# 4_port_powered_backplane.net
KiCad netlist of a schematic drawn in EAGLE
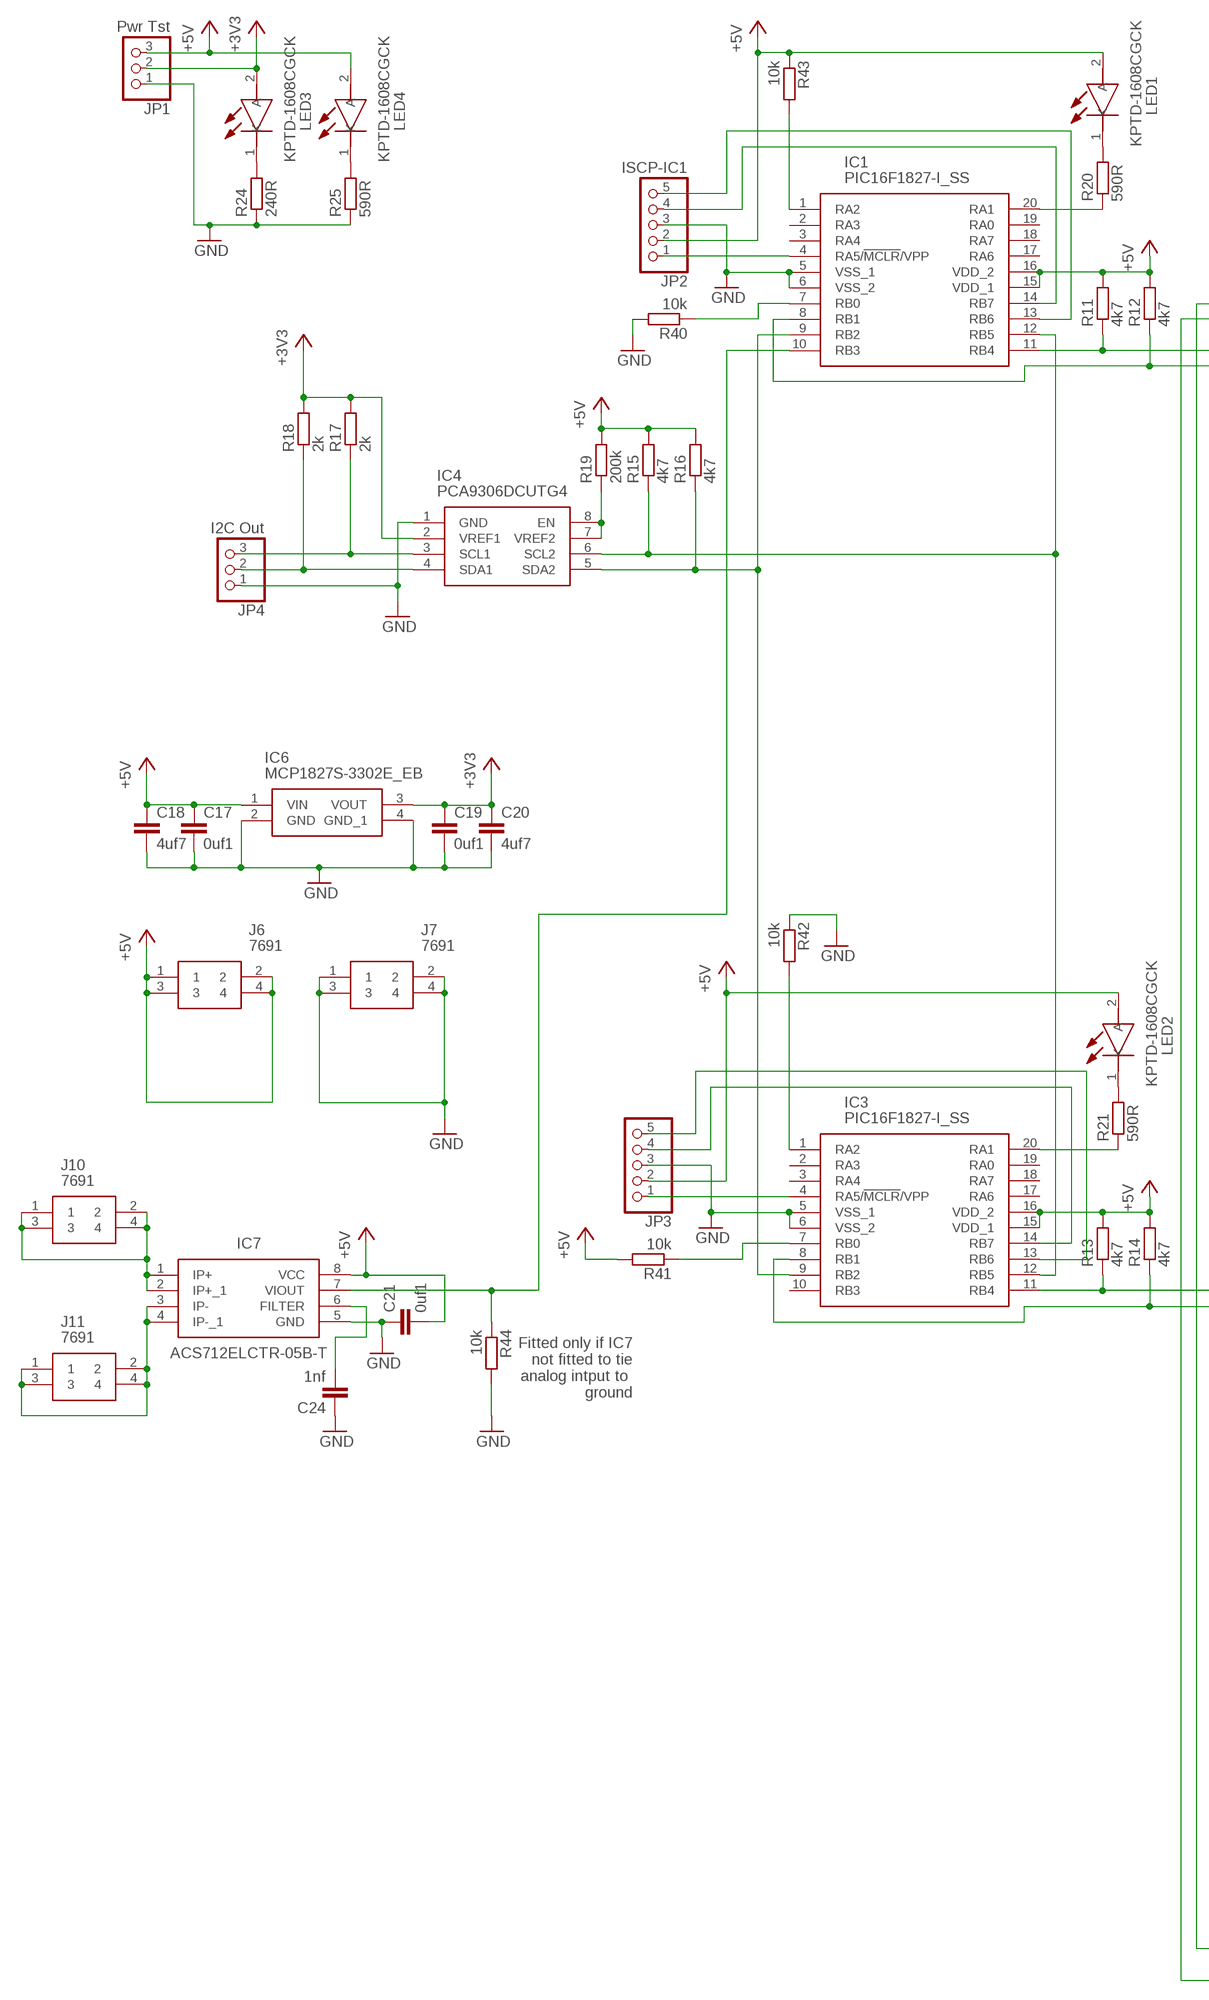
[diagram p0: schematic, sheet 1, part 1 of 2]
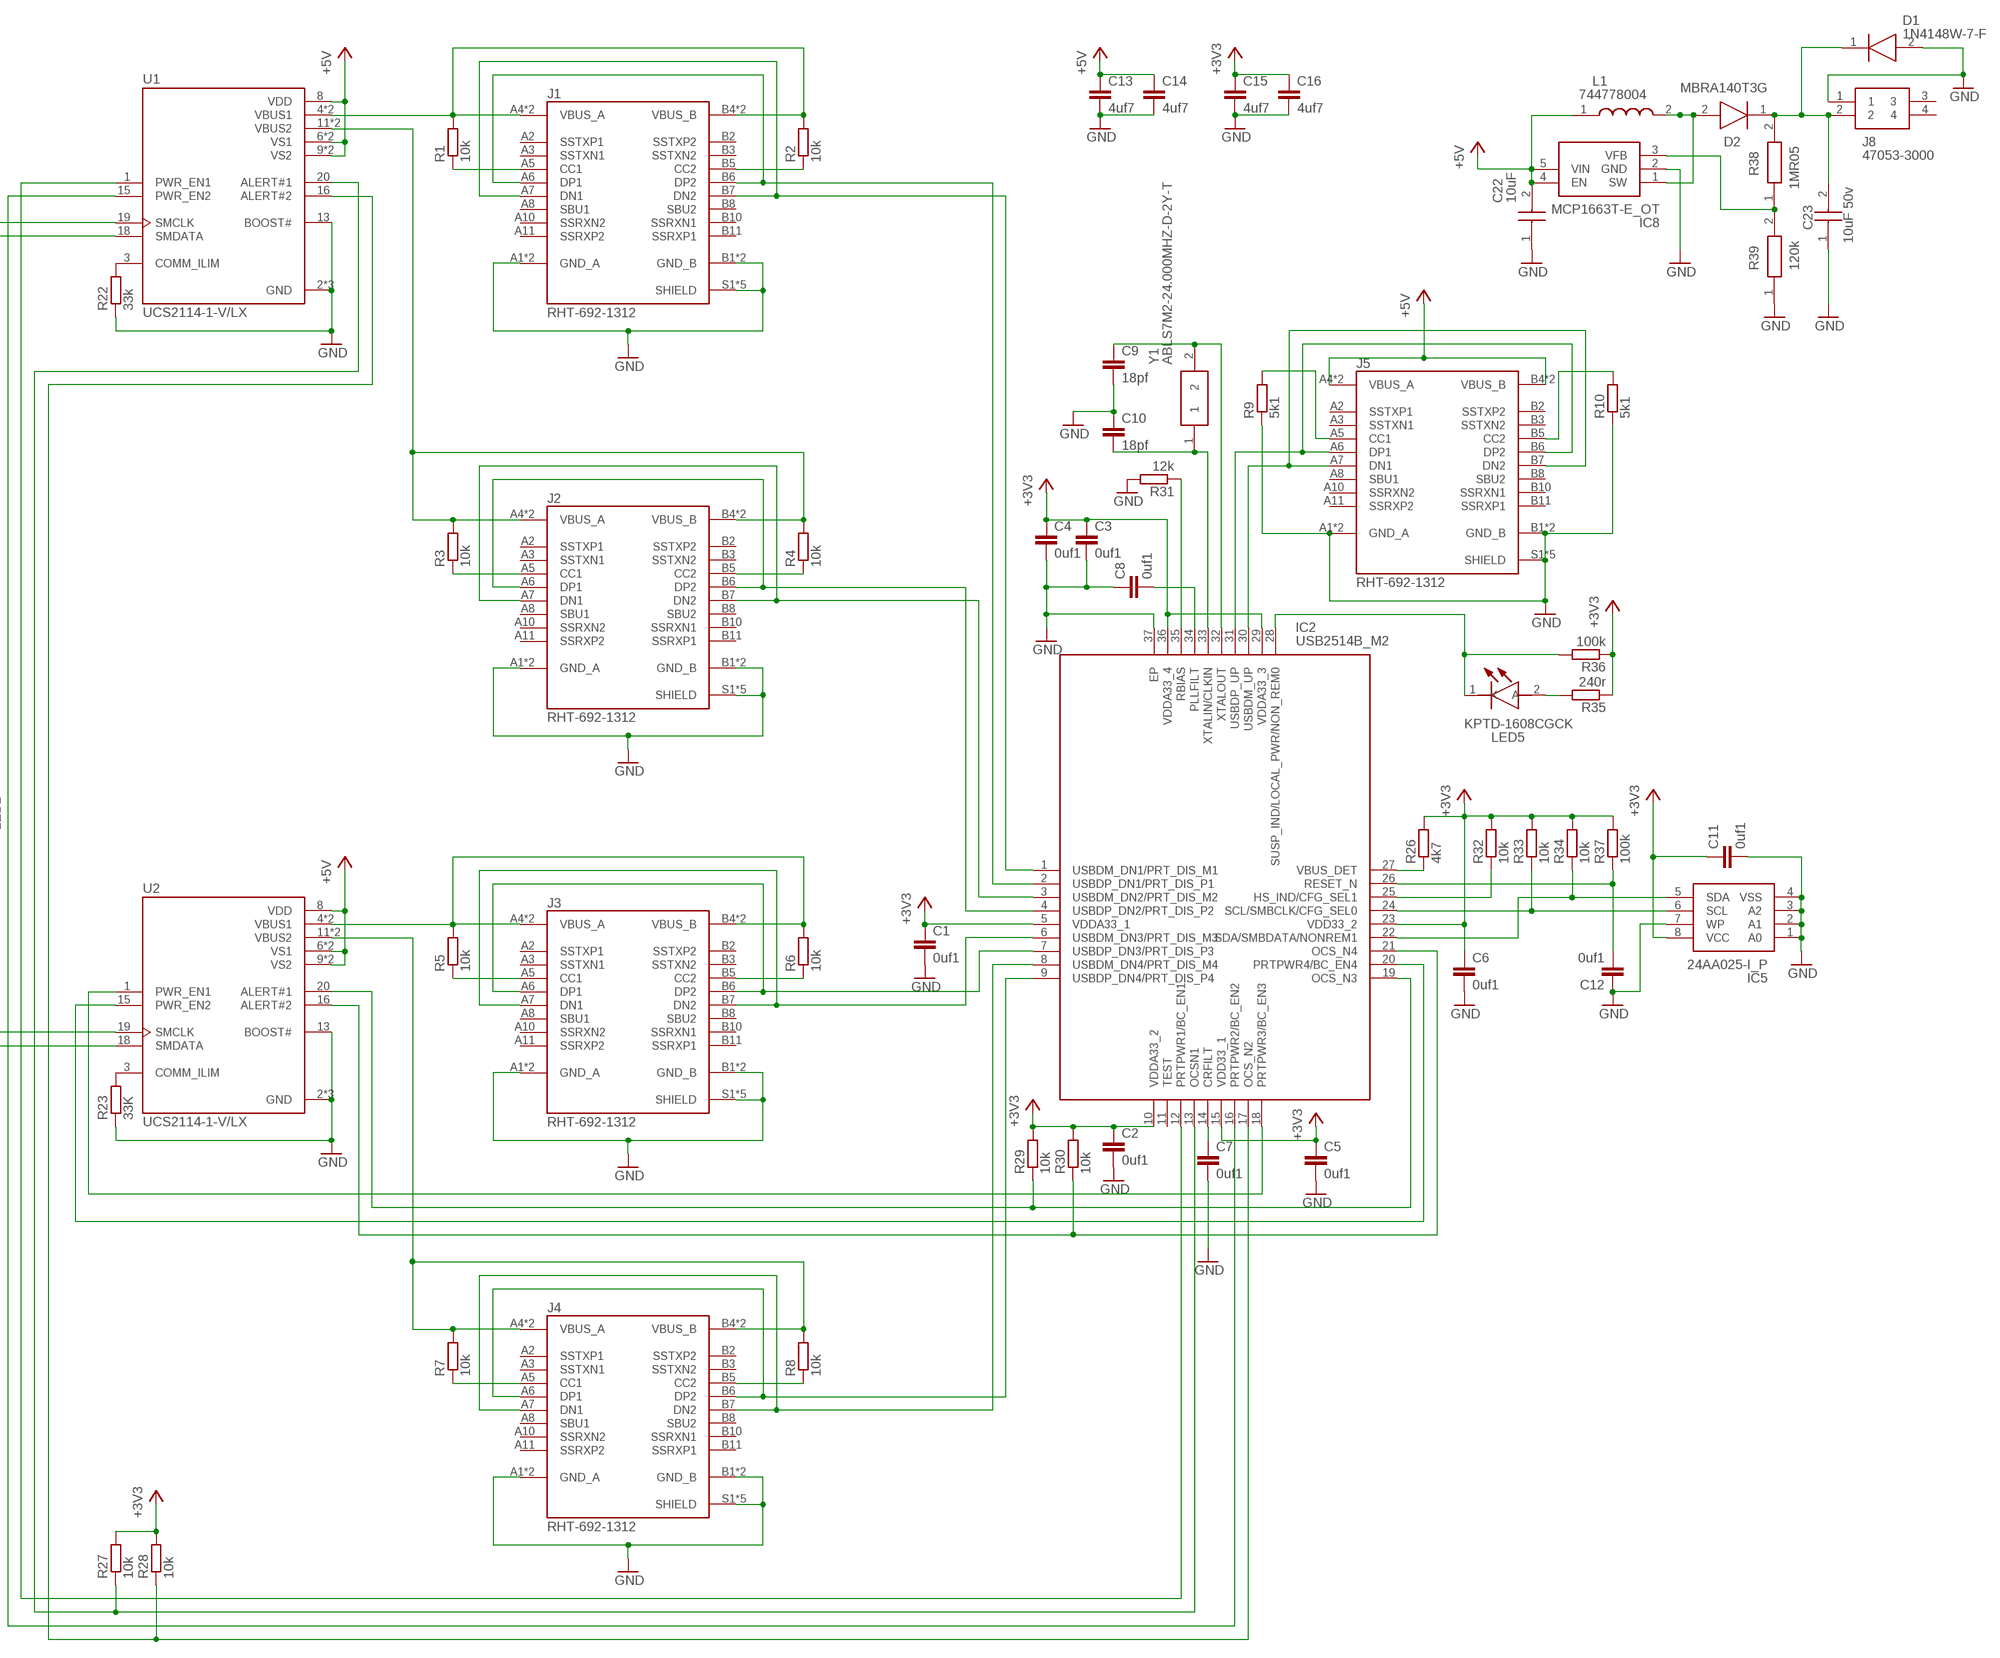
[diagram p1: schematic, sheet 1, part 2 of 2]

(export (version "E")
  (design (tool "Eeschema 10.0.6"))
  (components
    (comp (ref "C1")
      (value "0uf1")
      (footprint "eagle-import:C0603")
      (libsource (lib "eagle-import") (part "C-EUC0603"))
    )
    (comp (ref "C2")
      (value "0uf1")
      (footprint "eagle-import:C0603")
      (libsource (lib "eagle-import") (part "C-EUC0603"))
    )
    (comp (ref "C3")
      (value "0uf1")
      (footprint "eagle-import:C0603")
      (libsource (lib "eagle-import") (part "C-EUC0603"))
    )
    (comp (ref "C4")
      (value "0uf1")
      (footprint "eagle-import:C0603")
      (libsource (lib "eagle-import") (part "C-EUC0603"))
    )
    (comp (ref "C5")
      (value "0uf1")
      (footprint "eagle-import:C0603")
      (libsource (lib "eagle-import") (part "C-EUC0603"))
    )
    (comp (ref "C6")
      (value "0uf1")
      (footprint "eagle-import:C0603")
      (libsource (lib "eagle-import") (part "C-EUC0603"))
    )
    (comp (ref "C7")
      (value "0uf1")
      (footprint "eagle-import:C0603")
      (libsource (lib "eagle-import") (part "C-EUC0603"))
    )
    (comp (ref "C8")
      (value "0uf1")
      (footprint "eagle-import:C0603")
      (libsource (lib "eagle-import") (part "C-EUC0603"))
    )
    (comp (ref "C9")
      (value "18pf")
      (footprint "eagle-import:C0603")
      (libsource (lib "eagle-import") (part "C-EUC0603"))
    )
    (comp (ref "C10")
      (value "18pf")
      (footprint "eagle-import:C0603")
      (libsource (lib "eagle-import") (part "C-EUC0603"))
    )
    (comp (ref "C11")
      (value "0uf1")
      (footprint "eagle-import:C0603")
      (libsource (lib "eagle-import") (part "C-EUC0603"))
    )
    (comp (ref "C12")
      (value "0uf1")
      (footprint "eagle-import:C0603")
      (libsource (lib "eagle-import") (part "C-EUC0603"))
    )
    (comp (ref "C13")
      (value "4uf7")
      (footprint "eagle-import:C0603")
      (libsource (lib "eagle-import") (part "C-EUC0603"))
    )
    (comp (ref "C14")
      (value "4uf7")
      (footprint "eagle-import:C0603")
      (libsource (lib "eagle-import") (part "C-EUC0603"))
    )
    (comp (ref "C15")
      (value "4uf7")
      (footprint "eagle-import:C0603")
      (libsource (lib "eagle-import") (part "C-EUC0603"))
    )
    (comp (ref "C16")
      (value "4uf7")
      (footprint "eagle-import:C0603")
      (libsource (lib "eagle-import") (part "C-EUC0603"))
    )
    (comp (ref "C17")
      (value "0uf1")
      (footprint "eagle-import:C0603")
      (libsource (lib "eagle-import") (part "C-EUC0603"))
    )
    (comp (ref "C18")
      (value "4uf7")
      (footprint "eagle-import:C0603")
      (libsource (lib "eagle-import") (part "C-EUC0603"))
    )
    (comp (ref "C19")
      (value "0uf1")
      (footprint "eagle-import:C0603")
      (libsource (lib "eagle-import") (part "C-EUC0603"))
    )
    (comp (ref "C20")
      (value "4uf7")
      (footprint "eagle-import:C0603")
      (libsource (lib "eagle-import") (part "C-EUC0603"))
    )
    (comp (ref "C21")
      (value "0uf1")
      (footprint "eagle-import:C0603")
      (libsource (lib "eagle-import") (part "C-EUC0603"))
    )
    (comp (ref "C22")
      (value "10uF")
      (footprint "eagle-import:CAPC2012X145N")
      (fields
        (field (name "MANUFACTURER_PART_NUMBER") "C2012X7R1A106K125AC")
        (field (name "MOUSER_PART_NUMBER") "810-C2012X7R1A106K")
        (field (name "RS_PART_NUMBER") "7883017P")
      )
      (libsource (lib "eagle-import") (part "C2012X7R1A106K125AC"))
    )
    (comp (ref "C23")
      (value "10uF 50v")
      (footprint "eagle-import:CAPC3225X230N")
      (fields
        (field (name "MANUFACTURER_PART_NUMBER") "C3225X7R1H106M250AC")
        (field (name "MOUSER_PART_NUMBER") "810-C3225X7R1H106MAC")
        (field (name "RS_PART_NUMBER") "9163024P")
      )
      (libsource (lib "eagle-import") (part "C3225X7R1H106M250AC"))
    )
    (comp (ref "C24")
      (value "1nf")
      (footprint "eagle-import:C0603")
      (libsource (lib "eagle-import") (part "C-EUC0603"))
    )
    (comp (ref "D1")
      (value "1N4148W-7-F")
      (footprint "eagle-import:SOD3716X115N")
      (fields (field (name "MOUSER_PART_NUMBER") "621-1N4148W-F") (field (name "RS_PART_NUMBER") "7384728P"))
      (libsource (lib "eagle-import") (part "1N4148W-7-F"))
    )
    (comp (ref "D2")
      (value "MBRA140T3G")
      (footprint "eagle-import:DIOM5226X220N")
      (fields (field (name "MOUSER_PART_NUMBER") "863-MBRA140T3G") (field (name "RS_PART_NUMBER") "6255650P"))
      (libsource (lib "eagle-import") (part "MBRA140T3G"))
    )
    (comp (ref "IC1")
      (value "PIC16F1827-I_SS")
      (footprint "eagle-import:SOP65P780X200-20N")
      (fields
        (field (name "MANUFACTURER_PART_NUMBER") "PIC16F1827-I/SS")
        (field (name "MOUSER_PART_NUMBER") "579-PIC16F1827-I/SS")
        (field (name "RS_PART_NUMBER") "6988962P")
      )
      (libsource (lib "eagle-import") (part "PIC16F1827-I_SS"))
    )
    (comp (ref "IC2")
      (value "USB2514B_M2")
      (footprint "eagle-import:QFN50P600X600X100-37N")
      (fields
        (field (name "MANUFACTURER_PART_NUMBER") "USB2514B/M2")
        (field (name "MOUSER_PART_NUMBER") "579-USB2514B/M2")
      )
      (libsource (lib "eagle-import") (part "USB2514B_M2"))
    )
    (comp (ref "IC3")
      (value "PIC16F1827-I_SS")
      (footprint "eagle-import:SOP65P780X200-20N")
      (fields
        (field (name "MANUFACTURER_PART_NUMBER") "PIC16F1827-I/SS")
        (field (name "MOUSER_PART_NUMBER") "579-PIC16F1827-I/SS")
        (field (name "RS_PART_NUMBER") "6988962P")
      )
      (libsource (lib "eagle-import") (part "PIC16F1827-I_SS"))
    )
    (comp (ref "IC4")
      (value "PCA9306DCUTG4")
      (footprint "eagle-import:SOP50P310X90-8N")
      (fields (field (name "MOUSER_PART_NUMBER") "595-PCA9306DCUTG4"))
      (libsource (lib "eagle-import") (part "PCA9306DCUTG4"))
    )
    (comp (ref "IC5")
      (value "24AA025-I_P")
      (footprint "eagle-import:DIP781W56P254L950H533Q8N")
      (fields (field (name "ARROW_PART_NUMBER") "24AA025-I/P"))
      (libsource (lib "eagle-import") (part "24AA025-I_P"))
    )
    (comp (ref "IC6")
      (value "MCP1827S-3302E_EB")
      (footprint "eagle-import:TO254P1491X508-4N")
      (fields
        (field (name "MANUFACTURER_PART_NUMBER") "MCP1827S-3302E/EB")
        (field (name "RS_PART_NUMBER") "1458978")
      )
      (libsource (lib "eagle-import") (part "MCP1827S-3302E_EB"))
    )
    (comp (ref "IC7")
      (value "ACS712ELCTR-05B-T")
      (footprint "eagle-import:SOIC127P600X175-8N")
      (fields (field (name "RS_PART_NUMBER") "6807131"))
      (libsource (lib "eagle-import") (part "ACS712ELCTR-05B-T"))
    )
    (comp (ref "IC8")
      (value "MCP1663T-E_OT")
      (footprint "eagle-import:SOT95P270X145-5N")
      (fields
        (field (name "MANUFACTURER_PART_NUMBER") "MCP1663T-E/OT")
        (field (name "MOUSER_PART_NUMBER") "579-MCP1663T-E/OT")
      )
      (libsource (lib "eagle-import") (part "MCP1663T-E_OT"))
    )
    (comp (ref "J1")
      (value "RHT-692-1312")
      (footprint "eagle-import:RENHOTEC_RHT-692-1312")
      (fields (field (name "MF") "Renhotec"))
      (libsource (lib "eagle-import") (part "RHT-692-1312"))
    )
    (comp (ref "J2")
      (value "RHT-692-1312")
      (footprint "eagle-import:RENHOTEC_RHT-692-1312")
      (fields (field (name "MF") "Renhotec"))
      (libsource (lib "eagle-import") (part "RHT-692-1312"))
    )
    (comp (ref "J3")
      (value "RHT-692-1312")
      (footprint "eagle-import:RENHOTEC_RHT-692-1312")
      (fields (field (name "MF") "Renhotec"))
      (libsource (lib "eagle-import") (part "RHT-692-1312"))
    )
    (comp (ref "J4")
      (value "RHT-692-1312")
      (footprint "eagle-import:RENHOTEC_RHT-692-1312")
      (fields (field (name "MF") "Renhotec"))
      (libsource (lib "eagle-import") (part "RHT-692-1312"))
    )
    (comp (ref "J5")
      (value "RHT-692-1312")
      (footprint "eagle-import:RENHOTEC_RHT-692-1312")
      (fields (field (name "MF") "Renhotec"))
      (libsource (lib "eagle-import") (part "RHT-692-1312"))
    )
    (comp (ref "J6")
      (value "7691")
      (footprint "eagle-import:7691")
      (fields (field (name "RS_PART_NUMBER") "4096566"))
      (libsource (lib "eagle-import") (part "7691"))
    )
    (comp (ref "J7")
      (value "7691")
      (footprint "eagle-import:7691")
      (fields (field (name "RS_PART_NUMBER") "4096566"))
      (libsource (lib "eagle-import") (part "7691"))
    )
    (comp (ref "J8")
      (value "47053-3000")
      (footprint "eagle-import:470533000")
      (fields (field (name "MOUSER_PART_NUMBER") "538-47053-3000"))
      (libsource (lib "eagle-import") (part "47053-3000"))
    )
    (comp (ref "J10")
      (value "7691")
      (footprint "eagle-import:7691")
      (fields (field (name "RS_PART_NUMBER") "4096566"))
      (libsource (lib "eagle-import") (part "7691"))
    )
    (comp (ref "J11")
      (value "7691")
      (footprint "eagle-import:7691")
      (fields (field (name "RS_PART_NUMBER") "4096566"))
      (libsource (lib "eagle-import") (part "7691"))
    )
    (comp (ref "JP1")
      (value "Pwr Tst")
      (footprint "eagle-import:1X03")
      (libsource (lib "eagle-import") (part "PINHD-1X3"))
    )
    (comp (ref "JP2")
      (value "ISCP-IC1")
      (footprint "eagle-import:1X05")
      (libsource (lib "eagle-import") (part "PINHD-1X5"))
    )
    (comp (ref "JP3")
      (value "PINHD-1X5")
      (footprint "eagle-import:1X05")
      (libsource (lib "eagle-import") (part "PINHD-1X5"))
    )
    (comp (ref "JP4")
      (value "I2C Out")
      (footprint "eagle-import:1X03")
      (libsource (lib "eagle-import") (part "PINHD-1X3"))
    )
    (comp (ref "L1")
      (value "744778004")
      (footprint "eagle-import:744778004")
      (fields (field (name "MOUSER_PART_NUMBER") "710-744778004") (field (name "RS_PART_NUMBER") "7444927P"))
      (libsource (lib "eagle-import") (part "744778004"))
    )
    (comp (ref "LED1")
      (value "KPTD-1608CGCK")
      (footprint "eagle-import:LEDC1608X85N")
      (fields (field (name "RS_PART_NUMBER") "8609056P"))
      (libsource (lib "eagle-import") (part "KPTD-1608CGCK"))
    )
    (comp (ref "LED2")
      (value "KPTD-1608CGCK")
      (footprint "eagle-import:LEDC1608X85N")
      (fields (field (name "RS_PART_NUMBER") "8609056P"))
      (libsource (lib "eagle-import") (part "KPTD-1608CGCK"))
    )
    (comp (ref "LED3")
      (value "KPTD-1608CGCK")
      (footprint "eagle-import:LEDC1608X85N")
      (fields (field (name "RS_PART_NUMBER") "8609056P"))
      (libsource (lib "eagle-import") (part "KPTD-1608CGCK"))
    )
    (comp (ref "LED4")
      (value "KPTD-1608CGCK")
      (footprint "eagle-import:LEDC1608X85N")
      (fields (field (name "RS_PART_NUMBER") "8609056P"))
      (libsource (lib "eagle-import") (part "KPTD-1608CGCK"))
    )
    (comp (ref "LED5")
      (value "KPTD-1608CGCK")
      (footprint "eagle-import:LEDC1608X85N")
      (fields (field (name "RS_PART_NUMBER") "8609056P"))
      (libsource (lib "eagle-import") (part "KPTD-1608CGCK"))
    )
    (comp (ref "R1")
      (value "10k")
      (footprint "eagle-import:R0603")
      (libsource (lib "eagle-import") (part "R-EU_R0603"))
    )
    (comp (ref "R2")
      (value "10k")
      (footprint "eagle-import:R0603")
      (libsource (lib "eagle-import") (part "R-EU_R0603"))
    )
    (comp (ref "R3")
      (value "10k")
      (footprint "eagle-import:R0603")
      (libsource (lib "eagle-import") (part "R-EU_R0603"))
    )
    (comp (ref "R4")
      (value "10k")
      (footprint "eagle-import:R0603")
      (libsource (lib "eagle-import") (part "R-EU_R0603"))
    )
    (comp (ref "R5")
      (value "10k")
      (footprint "eagle-import:R0603")
      (libsource (lib "eagle-import") (part "R-EU_R0603"))
    )
    (comp (ref "R6")
      (value "10k")
      (footprint "eagle-import:R0603")
      (libsource (lib "eagle-import") (part "R-EU_R0603"))
    )
    (comp (ref "R7")
      (value "10k")
      (footprint "eagle-import:R0603")
      (libsource (lib "eagle-import") (part "R-EU_R0603"))
    )
    (comp (ref "R8")
      (value "10k")
      (footprint "eagle-import:R0603")
      (libsource (lib "eagle-import") (part "R-EU_R0603"))
    )
    (comp (ref "R9")
      (value "5k1")
      (footprint "eagle-import:R0603")
      (libsource (lib "eagle-import") (part "R-EU_R0603"))
    )
    (comp (ref "R10")
      (value "5k1")
      (footprint "eagle-import:R0603")
      (libsource (lib "eagle-import") (part "R-EU_R0603"))
    )
    (comp (ref "R11")
      (value "4k7")
      (footprint "eagle-import:R0603")
      (libsource (lib "eagle-import") (part "R-EU_R0603"))
    )
    (comp (ref "R12")
      (value "4k7")
      (footprint "eagle-import:R0603")
      (libsource (lib "eagle-import") (part "R-EU_R0603"))
    )
    (comp (ref "R13")
      (value "4k7")
      (footprint "eagle-import:R0603")
      (libsource (lib "eagle-import") (part "R-EU_R0603"))
    )
    (comp (ref "R14")
      (value "4k7")
      (footprint "eagle-import:R0603")
      (libsource (lib "eagle-import") (part "R-EU_R0603"))
    )
    (comp (ref "R15")
      (value "4k7")
      (footprint "eagle-import:R0603")
      (libsource (lib "eagle-import") (part "R-EU_R0603"))
    )
    (comp (ref "R16")
      (value "4k7")
      (footprint "eagle-import:R0603")
      (libsource (lib "eagle-import") (part "R-EU_R0603"))
    )
    (comp (ref "R17")
      (value "2k")
      (footprint "eagle-import:R0603")
      (libsource (lib "eagle-import") (part "R-EU_R0603"))
    )
    (comp (ref "R18")
      (value "2k")
      (footprint "eagle-import:R0603")
      (libsource (lib "eagle-import") (part "R-EU_R0603"))
    )
    (comp (ref "R19")
      (value "200k")
      (footprint "eagle-import:R0603")
      (libsource (lib "eagle-import") (part "R-EU_R0603"))
    )
    (comp (ref "R20")
      (value "590R")
      (footprint "eagle-import:R0603")
      (libsource (lib "eagle-import") (part "R-EU_R0603"))
    )
    (comp (ref "R21")
      (value "590R")
      (footprint "eagle-import:R0603")
      (libsource (lib "eagle-import") (part "R-EU_R0603"))
    )
    (comp (ref "R22")
      (value "33k")
      (footprint "eagle-import:R0603")
      (libsource (lib "eagle-import") (part "R-EU_R0603"))
    )
    (comp (ref "R23")
      (value "33K")
      (footprint "eagle-import:R0603")
      (libsource (lib "eagle-import") (part "R-EU_R0603"))
    )
    (comp (ref "R24")
      (value "240R")
      (footprint "eagle-import:R0603")
      (libsource (lib "eagle-import") (part "R-EU_R0603"))
    )
    (comp (ref "R25")
      (value "590R")
      (footprint "eagle-import:R0603")
      (libsource (lib "eagle-import") (part "R-EU_R0603"))
    )
    (comp (ref "R26")
      (value "4k7")
      (footprint "eagle-import:R0603")
      (libsource (lib "eagle-import") (part "R-EU_R0603"))
    )
    (comp (ref "R27")
      (value "10k")
      (footprint "eagle-import:R0603")
      (libsource (lib "eagle-import") (part "R-EU_R0603"))
    )
    (comp (ref "R28")
      (value "10k")
      (footprint "eagle-import:R0603")
      (libsource (lib "eagle-import") (part "R-EU_R0603"))
    )
    (comp (ref "R29")
      (value "10k")
      (footprint "eagle-import:R0603")
      (libsource (lib "eagle-import") (part "R-EU_R0603"))
    )
    (comp (ref "R30")
      (value "10k")
      (footprint "eagle-import:R0603")
      (libsource (lib "eagle-import") (part "R-EU_R0603"))
    )
    (comp (ref "R31")
      (value "12k")
      (footprint "eagle-import:R0603")
      (libsource (lib "eagle-import") (part "R-EU_R0603"))
    )
    (comp (ref "R32")
      (value "10k")
      (footprint "eagle-import:R0603")
      (libsource (lib "eagle-import") (part "R-EU_R0603"))
    )
    (comp (ref "R33")
      (value "10k")
      (footprint "eagle-import:R0603")
      (libsource (lib "eagle-import") (part "R-EU_R0603"))
    )
    (comp (ref "R34")
      (value "10k")
      (footprint "eagle-import:R0603")
      (libsource (lib "eagle-import") (part "R-EU_R0603"))
    )
    (comp (ref "R35")
      (value "240r")
      (footprint "eagle-import:R0603")
      (libsource (lib "eagle-import") (part "R-EU_R0603"))
    )
    (comp (ref "R36")
      (value "100k")
      (footprint "eagle-import:R0603")
      (libsource (lib "eagle-import") (part "R-EU_R0603"))
    )
    (comp (ref "R37")
      (value "100k")
      (footprint "eagle-import:R0603")
      (libsource (lib "eagle-import") (part "R-EU_R0603"))
    )
    (comp (ref "R38")
      (value "1MR05")
      (footprint "eagle-import:RESC2012X70N")
      (fields
        (field (name "MANUFACTURER_PART_NUMBER") "ERJ6ENF1054V")
        (field (name "RS_PART_NUMBER") "1140735")
      )
      (libsource (lib "eagle-import") (part "ERJ6ENF1054V"))
    )
    (comp (ref "R39")
      (value "120k")
      (footprint "eagle-import:RESC2012X70N")
      (fields
        (field (name "MANUFACTURER_PART_NUMBER") "ERJ6ENF1203V")
        (field (name "RS_PART_NUMBER") "7326075")
      )
      (libsource (lib "eagle-import") (part "ERJ6ENF1203V"))
    )
    (comp (ref "R40")
      (value "10k")
      (footprint "eagle-import:R0603")
      (libsource (lib "eagle-import") (part "R-EU_R0603"))
    )
    (comp (ref "R41")
      (value "10k")
      (footprint "eagle-import:R0603")
      (libsource (lib "eagle-import") (part "R-EU_R0603"))
    )
    (comp (ref "R42")
      (value "10k")
      (footprint "eagle-import:R0603")
      (libsource (lib "eagle-import") (part "R-EU_R0603"))
    )
    (comp (ref "R43")
      (value "10k")
      (footprint "eagle-import:R0603")
      (libsource (lib "eagle-import") (part "R-EU_R0603"))
    )
    (comp (ref "R44")
      (value "10k")
      (footprint "eagle-import:R0603")
      (libsource (lib "eagle-import") (part "R-EU_R0603"))
    )
    (comp (ref "U1")
      (value "UCS2114-1-V/LX")
      (footprint "eagle-import:IC_UCS2114-1-V_LX")
      (fields (field (name "MF") "Microchip Technology"))
      (libsource (lib "eagle-import") (part "UCS2114-1-V/LX"))
    )
    (comp (ref "U2")
      (value "UCS2114-1-V/LX")
      (footprint "eagle-import:IC_UCS2114-1-V_LX")
      (fields (field (name "MF") "Microchip Technology"))
      (libsource (lib "eagle-import") (part "UCS2114-1-V/LX"))
    )
    (comp (ref "Y1")
      (value "ABLS7M2-24.000MHZ-D-2Y-T")
      (footprint "eagle-import:ABLS7M2")
      (fields (field (name "MOUSER_PART_NUMBER") "815-ABLS7M2-24D2YT"))
      (libsource (lib "eagle-import") (part "ABLS7M2-24.000MHZ-D-2Y-T"))
    )
  )
  (nets
    (net (code "1") (name "+3V3") (class "Default")
      (node (ref "C1") (pin "1") (pinfunction "1_1") (pintype "passive"))
      (node (ref "C11") (pin "1") (pinfunction "1_1") (pintype "passive"))
      (node (ref "C15") (pin "1") (pinfunction "1_1") (pintype "passive"))
      (node (ref "C16") (pin "1") (pinfunction "1_1") (pintype "passive"))
      (node (ref "C19") (pin "1") (pinfunction "1_1") (pintype "passive"))
      (node (ref "C2") (pin "1") (pinfunction "1_1") (pintype "passive"))
      (node (ref "C20") (pin "1") (pinfunction "1_1") (pintype "passive"))
      (node (ref "C3") (pin "1") (pinfunction "1_1") (pintype "passive"))
      (node (ref "C4") (pin "1") (pinfunction "1_1") (pintype "passive"))
      (node (ref "C5") (pin "1") (pinfunction "1_1") (pintype "passive"))
      (node (ref "C6") (pin "1") (pinfunction "1_1") (pintype "passive"))
      (node (ref "IC2") (pin "10") (pinfunction "VDDA33_2_10") (pintype "bidirectional"))
      (node (ref "IC2") (pin "15") (pinfunction "VDD33_1_15") (pintype "bidirectional"))
      (node (ref "IC2") (pin "23") (pinfunction "VDD33_2_23") (pintype "bidirectional"))
      (node (ref "IC2") (pin "29") (pinfunction "VDDA33_3_29") (pintype "bidirectional"))
      (node (ref "IC2") (pin "36") (pinfunction "VDDA33_4_36") (pintype "bidirectional"))
      (node (ref "IC2") (pin "5") (pinfunction "VDDA33_1_5") (pintype "bidirectional"))
      (node (ref "IC4") (pin "2") (pinfunction "VREF1_2") (pintype "bidirectional"))
      (node (ref "IC5") (pin "8") (pinfunction "VCC_8") (pintype "bidirectional"))
      (node (ref "IC6") (pin "3") (pinfunction "VOUT_3") (pintype "power_in"))
      (node (ref "JP1") (pin "2") (pinfunction "2_2") (pintype "passive"))
      (node (ref "LED3") (pin "2") (pinfunction "A_2") (pintype "input"))
      (node (ref "R17") (pin "2") (pinfunction "2_2") (pintype "passive"))
      (node (ref "R18") (pin "2") (pinfunction "2_2") (pintype "passive"))
      (node (ref "R26") (pin "2") (pinfunction "2_2") (pintype "passive"))
      (node (ref "R27") (pin "2") (pinfunction "2_2") (pintype "passive"))
      (node (ref "R28") (pin "2") (pinfunction "2_2") (pintype "passive"))
      (node (ref "R29") (pin "2") (pinfunction "2_2") (pintype "passive"))
      (node (ref "R30") (pin "2") (pinfunction "2_2") (pintype "passive"))
      (node (ref "R32") (pin "2") (pinfunction "2_2") (pintype "passive"))
      (node (ref "R33") (pin "2") (pinfunction "2_2") (pintype "passive"))
      (node (ref "R34") (pin "2") (pinfunction "2_2") (pintype "passive"))
      (node (ref "R35") (pin "1") (pinfunction "1_1") (pintype "passive"))
      (node (ref "R36") (pin "1") (pinfunction "1_1") (pintype "passive"))
      (node (ref "R37") (pin "2") (pinfunction "2_2") (pintype "passive"))
    )
    (net (code "2") (name "+5V") (class "Default")
      (node (ref "C13") (pin "1") (pinfunction "1_1") (pintype "passive"))
      (node (ref "C14") (pin "1") (pinfunction "1_1") (pintype "passive"))
      (node (ref "C17") (pin "1") (pinfunction "1_1") (pintype "passive"))
      (node (ref "C18") (pin "1") (pinfunction "1_1") (pintype "passive"))
      (node (ref "C21") (pin "2") (pinfunction "2_2") (pintype "passive"))
      (node (ref "C22") (pin "2") (pinfunction "2_2") (pintype "bidirectional"))
      (node (ref "IC1") (pin "15") (pinfunction "VDD_1_15") (pintype "bidirectional"))
      (node (ref "IC1") (pin "16") (pinfunction "VDD_2_16") (pintype "bidirectional"))
      (node (ref "IC3") (pin "15") (pinfunction "VDD_1_15") (pintype "bidirectional"))
      (node (ref "IC3") (pin "16") (pinfunction "VDD_2_16") (pintype "bidirectional"))
      (node (ref "IC6") (pin "1") (pinfunction "VIN_1") (pintype "input"))
      (node (ref "IC7") (pin "8") (pinfunction "VCC_8") (pintype "input"))
      (node (ref "IC8") (pin "4") (pinfunction "EN_4") (pintype "bidirectional"))
      (node (ref "IC8") (pin "5") (pinfunction "VIN_5") (pintype "bidirectional"))
      (node (ref "J5") (pin "A4") (pinfunction "VBUS_A_A4") (pintype "power_in"))
      (node (ref "J5") (pin "A9") (pinfunction "VBUS_A_A9") (pintype "power_in"))
      (node (ref "J5") (pin "B4") (pinfunction "VBUS_B_B4") (pintype "power_in"))
      (node (ref "J5") (pin "B9") (pinfunction "VBUS_B_B9") (pintype "power_in"))
      (node (ref "J6") (pin "1") (pinfunction "1_1") (pintype "input"))
      (node (ref "J6") (pin "2") (pinfunction "2_2") (pintype "input"))
      (node (ref "J6") (pin "3") (pinfunction "3_3") (pintype "input"))
      (node (ref "J6") (pin "4") (pinfunction "4_4") (pintype "input"))
      (node (ref "JP1") (pin "3") (pinfunction "3_3") (pintype "passive"))
      (node (ref "JP2") (pin "2") (pinfunction "2_2") (pintype "passive"))
      (node (ref "JP3") (pin "2") (pinfunction "2_2") (pintype "passive"))
      (node (ref "L1") (pin "1") (pinfunction "1_1") (pintype "bidirectional"))
      (node (ref "LED1") (pin "2") (pinfunction "A_2") (pintype "input"))
      (node (ref "LED2") (pin "2") (pinfunction "A_2") (pintype "input"))
      (node (ref "LED4") (pin "2") (pinfunction "A_2") (pintype "input"))
      (node (ref "R11") (pin "2") (pinfunction "2_2") (pintype "passive"))
      (node (ref "R12") (pin "2") (pinfunction "2_2") (pintype "passive"))
      (node (ref "R13") (pin "2") (pinfunction "2_2") (pintype "passive"))
      (node (ref "R14") (pin "2") (pinfunction "2_2") (pintype "passive"))
      (node (ref "R15") (pin "2") (pinfunction "2_2") (pintype "passive"))
      (node (ref "R16") (pin "2") (pinfunction "2_2") (pintype "passive"))
      (node (ref "R19") (pin "2") (pinfunction "2_2") (pintype "passive"))
      (node (ref "R41") (pin "2") (pinfunction "2_2") (pintype "passive"))
      (node (ref "R43") (pin "1") (pinfunction "1_1") (pintype "passive"))
      (node (ref "U1") (pin "10") (pinfunction "VS2_10") (pintype "power_in"))
      (node (ref "U1") (pin "6") (pinfunction "VS1_6") (pintype "power_in"))
      (node (ref "U1") (pin "7") (pinfunction "VS1_7") (pintype "power_in"))
      (node (ref "U1") (pin "8") (pinfunction "VDD_8") (pintype "power_in"))
      (node (ref "U1") (pin "9") (pinfunction "VS2_9") (pintype "power_in"))
      (node (ref "U2") (pin "10") (pinfunction "VS2_10") (pintype "power_in"))
      (node (ref "U2") (pin "6") (pinfunction "VS1_6") (pintype "power_in"))
      (node (ref "U2") (pin "7") (pinfunction "VS1_7") (pintype "power_in"))
      (node (ref "U2") (pin "8") (pinfunction "VDD_8") (pintype "power_in"))
      (node (ref "U2") (pin "9") (pinfunction "VS2_9") (pintype "power_in"))
    )
    (net (code "3") (name "GND") (class "Default")
      (node (ref "C1") (pin "2") (pinfunction "2_2") (pintype "passive"))
      (node (ref "C10") (pin "1") (pinfunction "1_1") (pintype "passive"))
      (node (ref "C11") (pin "2") (pinfunction "2_2") (pintype "passive"))
      (node (ref "C12") (pin "1") (pinfunction "1_1") (pintype "passive"))
      (node (ref "C13") (pin "2") (pinfunction "2_2") (pintype "passive"))
      (node (ref "C14") (pin "2") (pinfunction "2_2") (pintype "passive"))
      (node (ref "C15") (pin "2") (pinfunction "2_2") (pintype "passive"))
      (node (ref "C16") (pin "2") (pinfunction "2_2") (pintype "passive"))
      (node (ref "C17") (pin "2") (pinfunction "2_2") (pintype "passive"))
      (node (ref "C18") (pin "2") (pinfunction "2_2") (pintype "passive"))
      (node (ref "C19") (pin "2") (pinfunction "2_2") (pintype "passive"))
      (node (ref "C2") (pin "2") (pinfunction "2_2") (pintype "passive"))
      (node (ref "C20") (pin "2") (pinfunction "2_2") (pintype "passive"))
      (node (ref "C21") (pin "1") (pinfunction "1_1") (pintype "passive"))
      (node (ref "C22") (pin "1") (pinfunction "1_1") (pintype "bidirectional"))
      (node (ref "C23") (pin "1") (pinfunction "1_1") (pintype "bidirectional"))
      (node (ref "C24") (pin "1") (pinfunction "1_1") (pintype "passive"))
      (node (ref "C3") (pin "2") (pinfunction "2_2") (pintype "passive"))
      (node (ref "C4") (pin "2") (pinfunction "2_2") (pintype "passive"))
      (node (ref "C5") (pin "2") (pinfunction "2_2") (pintype "passive"))
      (node (ref "C6") (pin "2") (pinfunction "2_2") (pintype "passive"))
      (node (ref "C7") (pin "2") (pinfunction "2_2") (pintype "passive"))
      (node (ref "C8") (pin "1") (pinfunction "1_1") (pintype "passive"))
      (node (ref "C9") (pin "2") (pinfunction "2_2") (pintype "passive"))
      (node (ref "D1") (pin "2") (pinfunction "A_2") (pintype "bidirectional"))
      (node (ref "IC1") (pin "5") (pinfunction "VSS_1_5") (pintype "bidirectional"))
      (node (ref "IC1") (pin "6") (pinfunction "VSS_2_6") (pintype "bidirectional"))
      (node (ref "IC2") (pin "37") (pinfunction "EP_37") (pintype "bidirectional"))
      (node (ref "IC3") (pin "5") (pinfunction "VSS_1_5") (pintype "bidirectional"))
      (node (ref "IC3") (pin "6") (pinfunction "VSS_2_6") (pintype "bidirectional"))
      (node (ref "IC4") (pin "1") (pinfunction "GND_1") (pintype "bidirectional"))
      (node (ref "IC5") (pin "1") (pinfunction "A0_1") (pintype "bidirectional"))
      (node (ref "IC5") (pin "2") (pinfunction "A1_2") (pintype "bidirectional"))
      (node (ref "IC5") (pin "3") (pinfunction "A2_3") (pintype "bidirectional"))
      (node (ref "IC5") (pin "4") (pinfunction "VSS_4") (pintype "bidirectional"))
      (node (ref "IC5") (pin "7") (pinfunction "WP_7") (pintype "bidirectional"))
      (node (ref "IC6") (pin "2") (pinfunction "GND_2") (pintype "power_in"))
      (node (ref "IC6") (pin "4") (pinfunction "GND_1_4") (pintype "power_in"))
      (node (ref "IC7") (pin "5") (pinfunction "GND_5") (pintype "input"))
      (node (ref "IC8") (pin "2") (pinfunction "GND_2") (pintype "bidirectional"))
      (node (ref "J1") (pin "A1") (pinfunction "GND_A_A1") (pintype "power_in"))
      (node (ref "J1") (pin "A12") (pinfunction "GND_A_A12") (pintype "power_in"))
      (node (ref "J1") (pin "B1") (pinfunction "GND_B_B1") (pintype "power_in"))
      (node (ref "J1") (pin "B12") (pinfunction "GND_B_B12") (pintype "power_in"))
      (node (ref "J1") (pin "S1") (pinfunction "SHIELD_S1") (pintype "passive"))
      (node (ref "J1") (pin "S2") (pinfunction "SHIELD_S2") (pintype "passive"))
      (node (ref "J1") (pin "S3") (pinfunction "SHIELD_S3") (pintype "passive"))
      (node (ref "J1") (pin "S4") (pinfunction "SHIELD_S4") (pintype "passive"))
      (node (ref "J1") (pin "S5") (pinfunction "SHIELD_S5") (pintype "passive"))
      (node (ref "J2") (pin "A1") (pinfunction "GND_A_A1") (pintype "power_in"))
      (node (ref "J2") (pin "A12") (pinfunction "GND_A_A12") (pintype "power_in"))
      (node (ref "J2") (pin "B1") (pinfunction "GND_B_B1") (pintype "power_in"))
      (node (ref "J2") (pin "B12") (pinfunction "GND_B_B12") (pintype "power_in"))
      (node (ref "J2") (pin "S1") (pinfunction "SHIELD_S1") (pintype "passive"))
      (node (ref "J2") (pin "S2") (pinfunction "SHIELD_S2") (pintype "passive"))
      (node (ref "J2") (pin "S3") (pinfunction "SHIELD_S3") (pintype "passive"))
      (node (ref "J2") (pin "S4") (pinfunction "SHIELD_S4") (pintype "passive"))
      (node (ref "J2") (pin "S5") (pinfunction "SHIELD_S5") (pintype "passive"))
      (node (ref "J3") (pin "A1") (pinfunction "GND_A_A1") (pintype "power_in"))
      (node (ref "J3") (pin "A12") (pinfunction "GND_A_A12") (pintype "power_in"))
      (node (ref "J3") (pin "B1") (pinfunction "GND_B_B1") (pintype "power_in"))
      (node (ref "J3") (pin "B12") (pinfunction "GND_B_B12") (pintype "power_in"))
      (node (ref "J3") (pin "S1") (pinfunction "SHIELD_S1") (pintype "passive"))
      (node (ref "J3") (pin "S2") (pinfunction "SHIELD_S2") (pintype "passive"))
      (node (ref "J3") (pin "S3") (pinfunction "SHIELD_S3") (pintype "passive"))
      (node (ref "J3") (pin "S4") (pinfunction "SHIELD_S4") (pintype "passive"))
      (node (ref "J3") (pin "S5") (pinfunction "SHIELD_S5") (pintype "passive"))
      (node (ref "J4") (pin "A1") (pinfunction "GND_A_A1") (pintype "power_in"))
      (node (ref "J4") (pin "A12") (pinfunction "GND_A_A12") (pintype "power_in"))
      (node (ref "J4") (pin "B1") (pinfunction "GND_B_B1") (pintype "power_in"))
      (node (ref "J4") (pin "B12") (pinfunction "GND_B_B12") (pintype "power_in"))
      (node (ref "J4") (pin "S1") (pinfunction "SHIELD_S1") (pintype "passive"))
      (node (ref "J4") (pin "S2") (pinfunction "SHIELD_S2") (pintype "passive"))
      (node (ref "J4") (pin "S3") (pinfunction "SHIELD_S3") (pintype "passive"))
      (node (ref "J4") (pin "S4") (pinfunction "SHIELD_S4") (pintype "passive"))
      (node (ref "J4") (pin "S5") (pinfunction "SHIELD_S5") (pintype "passive"))
      (node (ref "J5") (pin "A1") (pinfunction "GND_A_A1") (pintype "power_in"))
      (node (ref "J5") (pin "A12") (pinfunction "GND_A_A12") (pintype "power_in"))
      (node (ref "J5") (pin "B1") (pinfunction "GND_B_B1") (pintype "power_in"))
      (node (ref "J5") (pin "B12") (pinfunction "GND_B_B12") (pintype "power_in"))
      (node (ref "J5") (pin "S1") (pinfunction "SHIELD_S1") (pintype "passive"))
      (node (ref "J5") (pin "S2") (pinfunction "SHIELD_S2") (pintype "passive"))
      (node (ref "J5") (pin "S3") (pinfunction "SHIELD_S3") (pintype "passive"))
      (node (ref "J5") (pin "S4") (pinfunction "SHIELD_S4") (pintype "passive"))
      (node (ref "J5") (pin "S5") (pinfunction "SHIELD_S5") (pintype "passive"))
      (node (ref "J7") (pin "1") (pinfunction "1_1") (pintype "input"))
      (node (ref "J7") (pin "2") (pinfunction "2_2") (pintype "input"))
      (node (ref "J7") (pin "3") (pinfunction "3_3") (pintype "input"))
      (node (ref "J7") (pin "4") (pinfunction "4_4") (pintype "input"))
      (node (ref "J8") (pin "1") (pinfunction "1_1") (pintype "bidirectional"))
      (node (ref "JP1") (pin "1") (pinfunction "1_1") (pintype "passive"))
      (node (ref "JP2") (pin "3") (pinfunction "3_3") (pintype "passive"))
      (node (ref "JP3") (pin "3") (pinfunction "3_3") (pintype "passive"))
      (node (ref "JP4") (pin "1") (pinfunction "1_1") (pintype "passive"))
      (node (ref "R10") (pin "1") (pinfunction "1_1") (pintype "passive"))
      (node (ref "R22") (pin "1") (pinfunction "1_1") (pintype "passive"))
      (node (ref "R23") (pin "1") (pinfunction "1_1") (pintype "passive"))
      (node (ref "R24") (pin "1") (pinfunction "1_1") (pintype "passive"))
      (node (ref "R25") (pin "1") (pinfunction "1_1") (pintype "passive"))
      (node (ref "R31") (pin "2") (pinfunction "2_2") (pintype "passive"))
      (node (ref "R39") (pin "1") (pinfunction "1_1") (pintype "bidirectional"))
      (node (ref "R40") (pin "2") (pinfunction "2_2") (pintype "passive"))
      (node (ref "R42") (pin "1") (pinfunction "1_1") (pintype "passive"))
      (node (ref "R44") (pin "2") (pinfunction "2_2") (pintype "passive"))
      (node (ref "R9") (pin "1") (pinfunction "1_1") (pintype "passive"))
      (node (ref "U1") (pin "13") (pinfunction "BOOST#_13") (pintype "output"))
      (node (ref "U1") (pin "14") (pinfunction "GND_14") (pintype "power_in"))
      (node (ref "U1") (pin "17") (pinfunction "GND_17") (pintype "power_in"))
      (node (ref "U1") (pin "2") (pinfunction "GND_2") (pintype "power_in"))
      (node (ref "U2") (pin "13") (pinfunction "BOOST#_13") (pintype "output"))
      (node (ref "U2") (pin "14") (pinfunction "GND_14") (pintype "power_in"))
      (node (ref "U2") (pin "17") (pinfunction "GND_17") (pintype "power_in"))
      (node (ref "U2") (pin "2") (pinfunction "GND_2") (pintype "power_in"))
    )
    (net (code "4") (name "Net-(D1-K)") (class "Default")
      (node (ref "C23") (pin "2") (pinfunction "2_2") (pintype "bidirectional"))
      (node (ref "D1") (pin "1") (pinfunction "K_1") (pintype "bidirectional"))
      (node (ref "D2") (pin "1") (pinfunction "K_1") (pintype "bidirectional"))
      (node (ref "J8") (pin "2") (pinfunction "2_2") (pintype "bidirectional"))
      (node (ref "R38") (pin "2") (pinfunction "2_2") (pintype "bidirectional"))
    )
    (net (code "5") (name "Net-(D2-A)") (class "Default")
      (node (ref "D2") (pin "2") (pinfunction "A_2") (pintype "bidirectional"))
      (node (ref "IC8") (pin "1") (pinfunction "SW_1") (pintype "bidirectional"))
      (node (ref "L1") (pin "2") (pinfunction "2_2") (pintype "bidirectional"))
    )
    (net (code "6") (name "Net-(IC1-RA1)") (class "Default")
      (node (ref "IC1") (pin "20") (pinfunction "RA1_20") (pintype "bidirectional"))
      (node (ref "R20") (pin "1") (pinfunction "1_1") (pintype "passive"))
    )
    (net (code "7") (name "Net-(IC1-RA2)") (class "Default")
      (node (ref "IC1") (pin "1") (pinfunction "RA2_1") (pintype "bidirectional"))
      (node (ref "R43") (pin "2") (pinfunction "2_2") (pintype "passive"))
    )
    (net (code "8") (name "Net-(IC1-RA5{slash}~{MCLR}{slash}VPP)") (class "Default")
      (node (ref "IC1") (pin "4") (pinfunction "RA5/~{MCLR}/VPP_4") (pintype "bidirectional"))
      (node (ref "JP2") (pin "1") (pinfunction "1_1") (pintype "passive"))
    )
    (net (code "9") (name "Net-(IC1-RB0)") (class "Default")
      (node (ref "IC1") (pin "7") (pinfunction "RB0_7") (pintype "bidirectional"))
      (node (ref "R40") (pin "1") (pinfunction "1_1") (pintype "passive"))
    )
    (net (code "10") (name "Net-(IC1-RB1)") (class "Default")
      (node (ref "IC1") (pin "8") (pinfunction "RB1_8") (pintype "bidirectional"))
      (node (ref "R12") (pin "1") (pinfunction "1_1") (pintype "passive"))
      (node (ref "U1") (pin "18") (pinfunction "SMDATA_18") (pintype "bidirectional"))
    )
    (net (code "11") (name "Net-(IC1-RB2)") (class "Default")
      (node (ref "IC1") (pin "9") (pinfunction "RB2_9") (pintype "bidirectional"))
      (node (ref "IC3") (pin "9") (pinfunction "RB2_9") (pintype "bidirectional"))
      (node (ref "IC4") (pin "5") (pinfunction "SDA2_5") (pintype "bidirectional"))
      (node (ref "R16") (pin "1") (pinfunction "1_1") (pintype "passive"))
    )
    (net (code "12") (name "Net-(IC1-RB3)") (class "Default")
      (node (ref "IC1") (pin "10") (pinfunction "RB3_10") (pintype "bidirectional"))
      (node (ref "IC7") (pin "7") (pinfunction "VIOUT_7") (pintype "input"))
      (node (ref "R44") (pin "1") (pinfunction "1_1") (pintype "passive"))
    )
    (net (code "13") (name "Net-(IC1-RB4)") (class "Default")
      (node (ref "IC1") (pin "11") (pinfunction "RB4_11") (pintype "bidirectional"))
      (node (ref "R11") (pin "1") (pinfunction "1_1") (pintype "passive"))
      (node (ref "U1") (pin "19") (pinfunction "SMCLK_19") (pintype "input"))
    )
    (net (code "14") (name "Net-(IC1-RB5)") (class "Default")
      (node (ref "IC1") (pin "12") (pinfunction "RB5_12") (pintype "bidirectional"))
      (node (ref "IC3") (pin "12") (pinfunction "RB5_12") (pintype "bidirectional"))
      (node (ref "IC4") (pin "6") (pinfunction "SCL2_6") (pintype "bidirectional"))
      (node (ref "R15") (pin "1") (pinfunction "1_1") (pintype "passive"))
    )
    (net (code "15") (name "Net-(IC1-RB6)") (class "Default")
      (node (ref "IC1") (pin "13") (pinfunction "RB6_13") (pintype "bidirectional"))
      (node (ref "JP2") (pin "5") (pinfunction "5_5") (pintype "passive"))
    )
    (net (code "16") (name "Net-(IC1-RB7)") (class "Default")
      (node (ref "IC1") (pin "14") (pinfunction "RB7_14") (pintype "bidirectional"))
      (node (ref "JP2") (pin "4") (pinfunction "4_4") (pintype "passive"))
    )
    (net (code "17") (name "Net-(IC2-CRFILT)") (class "Default")
      (node (ref "C7") (pin "1") (pinfunction "1_1") (pintype "passive"))
      (node (ref "IC2") (pin "14") (pinfunction "CRFILT_14") (pintype "bidirectional"))
    )
    (net (code "18") (name "Net-(IC2-HS_IND{slash}CFG_SEL1)") (class "Default")
      (node (ref "IC2") (pin "25") (pinfunction "HS_IND/CFG_SEL1_25") (pintype "bidirectional"))
      (node (ref "R32") (pin "1") (pinfunction "1_1") (pintype "passive"))
    )
    (net (code "19") (name "Net-(IC2-OCSN1)") (class "Default")
      (node (ref "IC2") (pin "13") (pinfunction "OCSN1_13") (pintype "bidirectional"))
      (node (ref "R27") (pin "1") (pinfunction "1_1") (pintype "passive"))
      (node (ref "U1") (pin "20") (pinfunction "ALERT#1_20") (pintype "output"))
    )
    (net (code "20") (name "Net-(IC2-OCS_N2)") (class "Default")
      (node (ref "IC2") (pin "17") (pinfunction "OCS_N2_17") (pintype "bidirectional"))
      (node (ref "R28") (pin "1") (pinfunction "1_1") (pintype "passive"))
      (node (ref "U1") (pin "16") (pinfunction "ALERT#2_16") (pintype "output"))
    )
    (net (code "21") (name "Net-(IC2-OCS_N3)") (class "Default")
      (node (ref "IC2") (pin "19") (pinfunction "OCS_N3_19") (pintype "bidirectional"))
      (node (ref "R29") (pin "1") (pinfunction "1_1") (pintype "passive"))
      (node (ref "U2") (pin "20") (pinfunction "ALERT#1_20") (pintype "output"))
    )
    (net (code "22") (name "Net-(IC2-OCS_N4)") (class "Default")
      (node (ref "IC2") (pin "21") (pinfunction "OCS_N4_21") (pintype "bidirectional"))
      (node (ref "R30") (pin "1") (pinfunction "1_1") (pintype "passive"))
      (node (ref "U2") (pin "16") (pinfunction "ALERT#2_16") (pintype "output"))
    )
    (net (code "23") (name "Net-(IC2-PLLFILT)") (class "Default")
      (node (ref "C8") (pin "2") (pinfunction "2_2") (pintype "passive"))
      (node (ref "IC2") (pin "34") (pinfunction "PLLFILT_34") (pintype "bidirectional"))
    )
    (net (code "24") (name "Net-(IC2-PRTPWR1{slash}BC_EN1)") (class "Default")
      (node (ref "IC2") (pin "12") (pinfunction "PRTPWR1/BC_EN1_12") (pintype "bidirectional"))
      (node (ref "U1") (pin "1") (pinfunction "PWR_EN1_1") (pintype "input"))
    )
    (net (code "25") (name "Net-(IC2-PRTPWR2{slash}BC_EN2)") (class "Default")
      (node (ref "IC2") (pin "16") (pinfunction "PRTPWR2/BC_EN2_16") (pintype "bidirectional"))
      (node (ref "U1") (pin "15") (pinfunction "PWR_EN2_15") (pintype "input"))
    )
    (net (code "26") (name "Net-(IC2-PRTPWR3{slash}BC_EN3)") (class "Default")
      (node (ref "IC2") (pin "18") (pinfunction "PRTPWR3/BC_EN3_18") (pintype "bidirectional"))
      (node (ref "U2") (pin "1") (pinfunction "PWR_EN1_1") (pintype "input"))
    )
    (net (code "27") (name "Net-(IC2-PRTPWR4{slash}BC_EN4)") (class "Default")
      (node (ref "IC2") (pin "20") (pinfunction "PRTPWR4/BC_EN4_20") (pintype "bidirectional"))
      (node (ref "U2") (pin "15") (pinfunction "PWR_EN2_15") (pintype "input"))
    )
    (net (code "28") (name "Net-(IC2-RBIAS)") (class "Default")
      (node (ref "IC2") (pin "35") (pinfunction "RBIAS_35") (pintype "bidirectional"))
      (node (ref "R31") (pin "1") (pinfunction "1_1") (pintype "passive"))
    )
    (net (code "29") (name "Net-(IC2-RESET_N)") (class "Default")
      (node (ref "C12") (pin "2") (pinfunction "2_2") (pintype "passive"))
      (node (ref "IC2") (pin "26") (pinfunction "RESET_N_26") (pintype "bidirectional"))
      (node (ref "R37") (pin "1") (pinfunction "1_1") (pintype "passive"))
    )
    (net (code "30") (name "Net-(IC2-SCL{slash}SMBCLK{slash}CFG_SEL0)") (class "Default")
      (node (ref "IC2") (pin "24") (pinfunction "SCL/SMBCLK/CFG_SEL0_24") (pintype "bidirectional"))
      (node (ref "IC5") (pin "6") (pinfunction "SCL_6") (pintype "bidirectional"))
      (node (ref "R33") (pin "1") (pinfunction "1_1") (pintype "passive"))
    )
    (net (code "31") (name "Net-(IC2-SDA{slash}SMBDATA{slash}NONREM1)") (class "Default")
      (node (ref "IC2") (pin "22") (pinfunction "SDA/SMBDATA/NONREM1_22") (pintype "bidirectional"))
      (node (ref "IC5") (pin "5") (pinfunction "SDA_5") (pintype "bidirectional"))
      (node (ref "R34") (pin "1") (pinfunction "1_1") (pintype "passive"))
    )
    (net (code "32") (name "Net-(IC2-SUSP_IND{slash}LOCAL_PWR{slash}NON_REM0)") (class "Default")
      (node (ref "IC2") (pin "28") (pinfunction "SUSP_IND/LOCAL_PWR/NON_REM0_28") (pintype "bidirectional"))
      (node (ref "LED5") (pin "1") (pinfunction "K_1") (pintype "output"))
      (node (ref "R36") (pin "2") (pinfunction "2_2") (pintype "passive"))
    )
    (net (code "33") (name "Net-(IC2-USBDM_DN1{slash}PRT_DIS_M1)") (class "Default")
      (node (ref "IC2") (pin "1") (pinfunction "USBDM_DN1/PRT_DIS_M1_1") (pintype "bidirectional"))
      (node (ref "J1") (pin "A7") (pinfunction "DN1_A7") (pintype "passive"))
      (node (ref "J1") (pin "B7") (pinfunction "DN2_B7") (pintype "passive"))
    )
    (net (code "34") (name "Net-(IC2-USBDM_DN2{slash}PRT_DIS_M2)") (class "Default")
      (node (ref "IC2") (pin "3") (pinfunction "USBDM_DN2/PRT_DIS_M2_3") (pintype "bidirectional"))
      (node (ref "J2") (pin "A7") (pinfunction "DN1_A7") (pintype "passive"))
      (node (ref "J2") (pin "B7") (pinfunction "DN2_B7") (pintype "passive"))
    )
    (net (code "35") (name "Net-(IC2-USBDM_DN3{slash}PRT_DIS_M3)") (class "Default")
      (node (ref "IC2") (pin "6") (pinfunction "USBDM_DN3/PRT_DIS_M3_6") (pintype "bidirectional"))
      (node (ref "J3") (pin "A7") (pinfunction "DN1_A7") (pintype "passive"))
      (node (ref "J3") (pin "B7") (pinfunction "DN2_B7") (pintype "passive"))
    )
    (net (code "36") (name "Net-(IC2-USBDM_DN4{slash}PRT_DIS_M4)") (class "Default")
      (node (ref "IC2") (pin "8") (pinfunction "USBDM_DN4/PRT_DIS_M4_8") (pintype "bidirectional"))
      (node (ref "J4") (pin "A7") (pinfunction "DN1_A7") (pintype "passive"))
      (node (ref "J4") (pin "B7") (pinfunction "DN2_B7") (pintype "passive"))
    )
    (net (code "37") (name "Net-(IC2-USBDM_UP)") (class "Default")
      (node (ref "IC2") (pin "30") (pinfunction "USBDM_UP_30") (pintype "bidirectional"))
      (node (ref "J5") (pin "A7") (pinfunction "DN1_A7") (pintype "passive"))
      (node (ref "J5") (pin "B7") (pinfunction "DN2_B7") (pintype "passive"))
    )
    (net (code "38") (name "Net-(IC2-USBDP_DN1{slash}PRT_DIS_P1)") (class "Default")
      (node (ref "IC2") (pin "2") (pinfunction "USBDP_DN1/PRT_DIS_P1_2") (pintype "bidirectional"))
      (node (ref "J1") (pin "A6") (pinfunction "DP1_A6") (pintype "passive"))
      (node (ref "J1") (pin "B6") (pinfunction "DP2_B6") (pintype "passive"))
    )
    (net (code "39") (name "Net-(IC2-USBDP_DN2{slash}PRT_DIS_P2)") (class "Default")
      (node (ref "IC2") (pin "4") (pinfunction "USBDP_DN2/PRT_DIS_P2_4") (pintype "bidirectional"))
      (node (ref "J2") (pin "A6") (pinfunction "DP1_A6") (pintype "passive"))
      (node (ref "J2") (pin "B6") (pinfunction "DP2_B6") (pintype "passive"))
    )
    (net (code "40") (name "Net-(IC2-USBDP_DN3{slash}PRT_DIS_P3)") (class "Default")
      (node (ref "IC2") (pin "7") (pinfunction "USBDP_DN3/PRT_DIS_P3_7") (pintype "bidirectional"))
      (node (ref "J3") (pin "A6") (pinfunction "DP1_A6") (pintype "passive"))
      (node (ref "J3") (pin "B6") (pinfunction "DP2_B6") (pintype "passive"))
    )
    (net (code "41") (name "Net-(IC2-USBDP_DN4{slash}PRT_DIS_P4)") (class "Default")
      (node (ref "IC2") (pin "9") (pinfunction "USBDP_DN4/PRT_DIS_P4_9") (pintype "bidirectional"))
      (node (ref "J4") (pin "A6") (pinfunction "DP1_A6") (pintype "passive"))
      (node (ref "J4") (pin "B6") (pinfunction "DP2_B6") (pintype "passive"))
    )
    (net (code "42") (name "Net-(IC2-USBDP_UP)") (class "Default")
      (node (ref "IC2") (pin "31") (pinfunction "USBDP_UP_31") (pintype "bidirectional"))
      (node (ref "J5") (pin "A6") (pinfunction "DP1_A6") (pintype "passive"))
      (node (ref "J5") (pin "B6") (pinfunction "DP2_B6") (pintype "passive"))
    )
    (net (code "43") (name "Net-(IC2-VBUS_DET)") (class "Default")
      (node (ref "IC2") (pin "27") (pinfunction "VBUS_DET_27") (pintype "bidirectional"))
      (node (ref "R26") (pin "1") (pinfunction "1_1") (pintype "passive"))
    )
    (net (code "44") (name "Net-(IC2-XTALIN{slash}CLKIN)") (class "Default")
      (node (ref "C10") (pin "2") (pinfunction "2_2") (pintype "passive"))
      (node (ref "IC2") (pin "33") (pinfunction "XTALIN/CLKIN_33") (pintype "bidirectional"))
      (node (ref "Y1") (pin "1") (pinfunction "1_1") (pintype "bidirectional"))
    )
    (net (code "45") (name "Net-(IC2-XTALOUT)") (class "Default")
      (node (ref "C9") (pin "1") (pinfunction "1_1") (pintype "passive"))
      (node (ref "IC2") (pin "32") (pinfunction "XTALOUT_32") (pintype "bidirectional"))
      (node (ref "Y1") (pin "2") (pinfunction "2_2") (pintype "bidirectional"))
    )
    (net (code "46") (name "Net-(IC3-RA1)") (class "Default")
      (node (ref "IC3") (pin "20") (pinfunction "RA1_20") (pintype "bidirectional"))
      (node (ref "R21") (pin "1") (pinfunction "1_1") (pintype "passive"))
    )
    (net (code "47") (name "Net-(IC3-RA2)") (class "Default")
      (node (ref "IC3") (pin "1") (pinfunction "RA2_1") (pintype "bidirectional"))
      (node (ref "R42") (pin "2") (pinfunction "2_2") (pintype "passive"))
    )
    (net (code "48") (name "Net-(IC3-RA5{slash}~{MCLR}{slash}VPP)") (class "Default")
      (node (ref "IC3") (pin "4") (pinfunction "RA5/~{MCLR}/VPP_4") (pintype "bidirectional"))
      (node (ref "JP3") (pin "1") (pinfunction "1_1") (pintype "passive"))
    )
    (net (code "49") (name "Net-(IC3-RB0)") (class "Default")
      (node (ref "IC3") (pin "7") (pinfunction "RB0_7") (pintype "bidirectional"))
      (node (ref "R41") (pin "1") (pinfunction "1_1") (pintype "passive"))
    )
    (net (code "50") (name "Net-(IC3-RB1)") (class "Default")
      (node (ref "IC3") (pin "8") (pinfunction "RB1_8") (pintype "bidirectional"))
      (node (ref "R14") (pin "1") (pinfunction "1_1") (pintype "passive"))
      (node (ref "U2") (pin "18") (pinfunction "SMDATA_18") (pintype "bidirectional"))
    )
    (net (code "51") (name "Net-(IC3-RB4)") (class "Default")
      (node (ref "IC3") (pin "11") (pinfunction "RB4_11") (pintype "bidirectional"))
      (node (ref "R13") (pin "1") (pinfunction "1_1") (pintype "passive"))
      (node (ref "U2") (pin "19") (pinfunction "SMCLK_19") (pintype "input"))
    )
    (net (code "52") (name "Net-(IC3-RB6)") (class "Default")
      (node (ref "IC3") (pin "13") (pinfunction "RB6_13") (pintype "bidirectional"))
      (node (ref "JP3") (pin "5") (pinfunction "5_5") (pintype "passive"))
    )
    (net (code "53") (name "Net-(IC3-RB7)") (class "Default")
      (node (ref "IC3") (pin "14") (pinfunction "RB7_14") (pintype "bidirectional"))
      (node (ref "JP3") (pin "4") (pinfunction "4_4") (pintype "passive"))
    )
    (net (code "54") (name "Net-(IC4-EN)") (class "Default")
      (node (ref "IC4") (pin "7") (pinfunction "VREF2_7") (pintype "bidirectional"))
      (node (ref "IC4") (pin "8") (pinfunction "EN_8") (pintype "bidirectional"))
      (node (ref "R19") (pin "1") (pinfunction "1_1") (pintype "passive"))
    )
    (net (code "55") (name "Net-(IC4-SCL1)") (class "Default")
      (node (ref "IC4") (pin "3") (pinfunction "SCL1_3") (pintype "bidirectional"))
      (node (ref "JP4") (pin "3") (pinfunction "3_3") (pintype "passive"))
      (node (ref "R17") (pin "1") (pinfunction "1_1") (pintype "passive"))
    )
    (net (code "56") (name "Net-(IC4-SDA1)") (class "Default")
      (node (ref "IC4") (pin "4") (pinfunction "SDA1_4") (pintype "bidirectional"))
      (node (ref "JP4") (pin "2") (pinfunction "2_2") (pintype "passive"))
      (node (ref "R18") (pin "1") (pinfunction "1_1") (pintype "passive"))
    )
    (net (code "57") (name "Net-(IC7-FILTER)") (class "Default")
      (node (ref "C24") (pin "2") (pinfunction "2_2") (pintype "passive"))
      (node (ref "IC7") (pin "6") (pinfunction "FILTER_6") (pintype "input"))
    )
    (net (code "58") (name "Net-(IC7-IP+)") (class "Default")
      (node (ref "IC7") (pin "1") (pinfunction "IP+_1") (pintype "input"))
      (node (ref "IC7") (pin "2") (pinfunction "IP+_1_2") (pintype "input"))
      (node (ref "J10") (pin "1") (pinfunction "1_1") (pintype "input"))
      (node (ref "J10") (pin "2") (pinfunction "2_2") (pintype "input"))
      (node (ref "J10") (pin "3") (pinfunction "3_3") (pintype "input"))
      (node (ref "J10") (pin "4") (pinfunction "4_4") (pintype "input"))
    )
    (net (code "59") (name "Net-(IC7-IP-)") (class "Default")
      (node (ref "IC7") (pin "3") (pinfunction "IP-_3") (pintype "input"))
      (node (ref "IC7") (pin "4") (pinfunction "IP-_1_4") (pintype "input"))
      (node (ref "J11") (pin "1") (pinfunction "1_1") (pintype "input"))
      (node (ref "J11") (pin "2") (pinfunction "2_2") (pintype "input"))
      (node (ref "J11") (pin "3") (pinfunction "3_3") (pintype "input"))
      (node (ref "J11") (pin "4") (pinfunction "4_4") (pintype "input"))
    )
    (net (code "60") (name "Net-(IC8-VFB)") (class "Default")
      (node (ref "IC8") (pin "3") (pinfunction "VFB_3") (pintype "bidirectional"))
      (node (ref "R38") (pin "1") (pinfunction "1_1") (pintype "bidirectional"))
      (node (ref "R39") (pin "2") (pinfunction "2_2") (pintype "bidirectional"))
    )
    (net (code "61") (name "Net-(J1-CC1)") (class "Default")
      (node (ref "J1") (pin "A5") (pinfunction "CC1_A5") (pintype "passive"))
      (node (ref "R1") (pin "1") (pinfunction "1_1") (pintype "passive"))
    )
    (net (code "62") (name "Net-(J1-CC2)") (class "Default")
      (node (ref "J1") (pin "B5") (pinfunction "CC2_B5") (pintype "passive"))
      (node (ref "R2") (pin "1") (pinfunction "1_1") (pintype "passive"))
    )
    (net (code "63") (name "Net-(J1-VBUS_A-PadA4)") (class "Default")
      (node (ref "J1") (pin "A4") (pinfunction "VBUS_A_A4") (pintype "power_in"))
      (node (ref "J1") (pin "A9") (pinfunction "VBUS_A_A9") (pintype "power_in"))
      (node (ref "J1") (pin "B4") (pinfunction "VBUS_B_B4") (pintype "power_in"))
      (node (ref "J1") (pin "B9") (pinfunction "VBUS_B_B9") (pintype "power_in"))
      (node (ref "R1") (pin "2") (pinfunction "2_2") (pintype "passive"))
      (node (ref "R2") (pin "2") (pinfunction "2_2") (pintype "passive"))
      (node (ref "U1") (pin "4") (pinfunction "VBUS1_4") (pintype "power_in"))
      (node (ref "U1") (pin "5") (pinfunction "VBUS1_5") (pintype "power_in"))
    )
    (net (code "64") (name "Net-(J2-CC1)") (class "Default")
      (node (ref "J2") (pin "A5") (pinfunction "CC1_A5") (pintype "passive"))
      (node (ref "R3") (pin "1") (pinfunction "1_1") (pintype "passive"))
    )
    (net (code "65") (name "Net-(J2-CC2)") (class "Default")
      (node (ref "J2") (pin "B5") (pinfunction "CC2_B5") (pintype "passive"))
      (node (ref "R4") (pin "1") (pinfunction "1_1") (pintype "passive"))
    )
    (net (code "66") (name "Net-(J2-VBUS_A-PadA4)") (class "Default")
      (node (ref "J2") (pin "A4") (pinfunction "VBUS_A_A4") (pintype "power_in"))
      (node (ref "J2") (pin "A9") (pinfunction "VBUS_A_A9") (pintype "power_in"))
      (node (ref "J2") (pin "B4") (pinfunction "VBUS_B_B4") (pintype "power_in"))
      (node (ref "J2") (pin "B9") (pinfunction "VBUS_B_B9") (pintype "power_in"))
      (node (ref "R3") (pin "2") (pinfunction "2_2") (pintype "passive"))
      (node (ref "R4") (pin "2") (pinfunction "2_2") (pintype "passive"))
      (node (ref "U1") (pin "11") (pinfunction "VBUS2_11") (pintype "power_in"))
      (node (ref "U1") (pin "12") (pinfunction "VBUS2_12") (pintype "power_in"))
    )
    (net (code "67") (name "Net-(J3-CC1)") (class "Default")
      (node (ref "J3") (pin "A5") (pinfunction "CC1_A5") (pintype "passive"))
      (node (ref "R5") (pin "1") (pinfunction "1_1") (pintype "passive"))
    )
    (net (code "68") (name "Net-(J3-CC2)") (class "Default")
      (node (ref "J3") (pin "B5") (pinfunction "CC2_B5") (pintype "passive"))
      (node (ref "R6") (pin "1") (pinfunction "1_1") (pintype "passive"))
    )
    (net (code "69") (name "Net-(J3-VBUS_A-PadA4)") (class "Default")
      (node (ref "J3") (pin "A4") (pinfunction "VBUS_A_A4") (pintype "power_in"))
      (node (ref "J3") (pin "A9") (pinfunction "VBUS_A_A9") (pintype "power_in"))
      (node (ref "J3") (pin "B4") (pinfunction "VBUS_B_B4") (pintype "power_in"))
      (node (ref "J3") (pin "B9") (pinfunction "VBUS_B_B9") (pintype "power_in"))
      (node (ref "R5") (pin "2") (pinfunction "2_2") (pintype "passive"))
      (node (ref "R6") (pin "2") (pinfunction "2_2") (pintype "passive"))
      (node (ref "U2") (pin "4") (pinfunction "VBUS1_4") (pintype "power_in"))
      (node (ref "U2") (pin "5") (pinfunction "VBUS1_5") (pintype "power_in"))
    )
    (net (code "70") (name "Net-(J4-CC1)") (class "Default")
      (node (ref "J4") (pin "A5") (pinfunction "CC1_A5") (pintype "passive"))
      (node (ref "R7") (pin "1") (pinfunction "1_1") (pintype "passive"))
    )
    (net (code "71") (name "Net-(J4-CC2)") (class "Default")
      (node (ref "J4") (pin "B5") (pinfunction "CC2_B5") (pintype "passive"))
      (node (ref "R8") (pin "1") (pinfunction "1_1") (pintype "passive"))
    )
    (net (code "72") (name "Net-(J4-VBUS_A-PadA4)") (class "Default")
      (node (ref "J4") (pin "A4") (pinfunction "VBUS_A_A4") (pintype "power_in"))
      (node (ref "J4") (pin "A9") (pinfunction "VBUS_A_A9") (pintype "power_in"))
      (node (ref "J4") (pin "B4") (pinfunction "VBUS_B_B4") (pintype "power_in"))
      (node (ref "J4") (pin "B9") (pinfunction "VBUS_B_B9") (pintype "power_in"))
      (node (ref "R7") (pin "2") (pinfunction "2_2") (pintype "passive"))
      (node (ref "R8") (pin "2") (pinfunction "2_2") (pintype "passive"))
      (node (ref "U2") (pin "11") (pinfunction "VBUS2_11") (pintype "power_in"))
      (node (ref "U2") (pin "12") (pinfunction "VBUS2_12") (pintype "power_in"))
    )
    (net (code "73") (name "Net-(J5-CC1)") (class "Default")
      (node (ref "J5") (pin "A5") (pinfunction "CC1_A5") (pintype "passive"))
      (node (ref "R9") (pin "2") (pinfunction "2_2") (pintype "passive"))
    )
    (net (code "74") (name "Net-(J5-CC2)") (class "Default")
      (node (ref "J5") (pin "B5") (pinfunction "CC2_B5") (pintype "passive"))
      (node (ref "R10") (pin "2") (pinfunction "2_2") (pintype "passive"))
    )
    (net (code "75") (name "Net-(LED1-K)") (class "Default")
      (node (ref "LED1") (pin "1") (pinfunction "K_1") (pintype "output"))
      (node (ref "R20") (pin "2") (pinfunction "2_2") (pintype "passive"))
    )
    (net (code "76") (name "Net-(LED2-K)") (class "Default")
      (node (ref "LED2") (pin "1") (pinfunction "K_1") (pintype "output"))
      (node (ref "R21") (pin "2") (pinfunction "2_2") (pintype "passive"))
    )
    (net (code "77") (name "Net-(LED3-K)") (class "Default")
      (node (ref "LED3") (pin "1") (pinfunction "K_1") (pintype "output"))
      (node (ref "R24") (pin "2") (pinfunction "2_2") (pintype "passive"))
    )
    (net (code "78") (name "Net-(LED4-K)") (class "Default")
      (node (ref "LED4") (pin "1") (pinfunction "K_1") (pintype "output"))
      (node (ref "R25") (pin "2") (pinfunction "2_2") (pintype "passive"))
    )
    (net (code "79") (name "Net-(LED5-A)") (class "Default")
      (node (ref "LED5") (pin "2") (pinfunction "A_2") (pintype "input"))
      (node (ref "R35") (pin "2") (pinfunction "2_2") (pintype "passive"))
    )
    (net (code "80") (name "Net-(U1-COMM_ILIM)") (class "Default")
      (node (ref "R22") (pin "2") (pinfunction "2_2") (pintype "passive"))
      (node (ref "U1") (pin "3") (pinfunction "COMM_ILIM_3") (pintype "bidirectional"))
    )
    (net (code "81") (name "Net-(U2-COMM_ILIM)") (class "Default")
      (node (ref "R23") (pin "2") (pinfunction "2_2") (pintype "passive"))
      (node (ref "U2") (pin "3") (pinfunction "COMM_ILIM_3") (pintype "bidirectional"))
    )
    (net (code "82") (name "unconnected-(IC1-RA0-Pad19)") (class "Default")
      (node (ref "IC1") (pin "19") (pinfunction "RA0_19") (pintype "bidirectional"))
    )
    (net (code "83") (name "unconnected-(IC1-RA3-Pad2)") (class "Default")
      (node (ref "IC1") (pin "2") (pinfunction "RA3_2") (pintype "bidirectional"))
    )
    (net (code "84") (name "unconnected-(IC1-RA4-Pad3)") (class "Default")
      (node (ref "IC1") (pin "3") (pinfunction "RA4_3") (pintype "bidirectional"))
    )
    (net (code "85") (name "unconnected-(IC1-RA6-Pad17)") (class "Default")
      (node (ref "IC1") (pin "17") (pinfunction "RA6_17") (pintype "bidirectional"))
    )
    (net (code "86") (name "unconnected-(IC1-RA7-Pad18)") (class "Default")
      (node (ref "IC1") (pin "18") (pinfunction "RA7_18") (pintype "bidirectional"))
    )
    (net (code "87") (name "unconnected-(IC2-TEST-Pad11)") (class "Default")
      (node (ref "IC2") (pin "11") (pinfunction "TEST_11") (pintype "bidirectional"))
    )
    (net (code "88") (name "unconnected-(IC3-RA0-Pad19)") (class "Default")
      (node (ref "IC3") (pin "19") (pinfunction "RA0_19") (pintype "bidirectional"))
    )
    (net (code "89") (name "unconnected-(IC3-RA3-Pad2)") (class "Default")
      (node (ref "IC3") (pin "2") (pinfunction "RA3_2") (pintype "bidirectional"))
    )
    (net (code "90") (name "unconnected-(IC3-RA4-Pad3)") (class "Default")
      (node (ref "IC3") (pin "3") (pinfunction "RA4_3") (pintype "bidirectional"))
    )
    (net (code "91") (name "unconnected-(IC3-RA6-Pad17)") (class "Default")
      (node (ref "IC3") (pin "17") (pinfunction "RA6_17") (pintype "bidirectional"))
    )
    (net (code "92") (name "unconnected-(IC3-RA7-Pad18)") (class "Default")
      (node (ref "IC3") (pin "18") (pinfunction "RA7_18") (pintype "bidirectional"))
    )
    (net (code "93") (name "unconnected-(IC3-RB3-Pad10)") (class "Default")
      (node (ref "IC3") (pin "10") (pinfunction "RB3_10") (pintype "bidirectional"))
    )
    (net (code "94") (name "unconnected-(J1-SBU1-PadA8)") (class "Default")
      (node (ref "J1") (pin "A8") (pinfunction "SBU1_A8") (pintype "passive"))
    )
    (net (code "95") (name "unconnected-(J1-SBU2-PadB8)") (class "Default")
      (node (ref "J1") (pin "B8") (pinfunction "SBU2_B8") (pintype "passive"))
    )
    (net (code "96") (name "unconnected-(J1-SSRXN1-PadB10)") (class "Default")
      (node (ref "J1") (pin "B10") (pinfunction "SSRXN1_B10") (pintype "passive"))
    )
    (net (code "97") (name "unconnected-(J1-SSRXN2-PadA10)") (class "Default")
      (node (ref "J1") (pin "A10") (pinfunction "SSRXN2_A10") (pintype "passive"))
    )
    (net (code "98") (name "unconnected-(J1-SSRXP1-PadB11)") (class "Default")
      (node (ref "J1") (pin "B11") (pinfunction "SSRXP1_B11") (pintype "passive"))
    )
    (net (code "99") (name "unconnected-(J1-SSRXP2-PadA11)") (class "Default")
      (node (ref "J1") (pin "A11") (pinfunction "SSRXP2_A11") (pintype "passive"))
    )
    (net (code "100") (name "unconnected-(J1-SSTXN1-PadA3)") (class "Default")
      (node (ref "J1") (pin "A3") (pinfunction "SSTXN1_A3") (pintype "passive"))
    )
    (net (code "101") (name "unconnected-(J1-SSTXN2-PadB3)") (class "Default")
      (node (ref "J1") (pin "B3") (pinfunction "SSTXN2_B3") (pintype "passive"))
    )
    (net (code "102") (name "unconnected-(J1-SSTXP1-PadA2)") (class "Default")
      (node (ref "J1") (pin "A2") (pinfunction "SSTXP1_A2") (pintype "passive"))
    )
    (net (code "103") (name "unconnected-(J1-SSTXP2-PadB2)") (class "Default")
      (node (ref "J1") (pin "B2") (pinfunction "SSTXP2_B2") (pintype "passive"))
    )
    (net (code "104") (name "unconnected-(J2-SBU1-PadA8)") (class "Default")
      (node (ref "J2") (pin "A8") (pinfunction "SBU1_A8") (pintype "passive"))
    )
    (net (code "105") (name "unconnected-(J2-SBU2-PadB8)") (class "Default")
      (node (ref "J2") (pin "B8") (pinfunction "SBU2_B8") (pintype "passive"))
    )
    (net (code "106") (name "unconnected-(J2-SSRXN1-PadB10)") (class "Default")
      (node (ref "J2") (pin "B10") (pinfunction "SSRXN1_B10") (pintype "passive"))
    )
    (net (code "107") (name "unconnected-(J2-SSRXN2-PadA10)") (class "Default")
      (node (ref "J2") (pin "A10") (pinfunction "SSRXN2_A10") (pintype "passive"))
    )
    (net (code "108") (name "unconnected-(J2-SSRXP1-PadB11)") (class "Default")
      (node (ref "J2") (pin "B11") (pinfunction "SSRXP1_B11") (pintype "passive"))
    )
    (net (code "109") (name "unconnected-(J2-SSRXP2-PadA11)") (class "Default")
      (node (ref "J2") (pin "A11") (pinfunction "SSRXP2_A11") (pintype "passive"))
    )
    (net (code "110") (name "unconnected-(J2-SSTXN1-PadA3)") (class "Default")
      (node (ref "J2") (pin "A3") (pinfunction "SSTXN1_A3") (pintype "passive"))
    )
    (net (code "111") (name "unconnected-(J2-SSTXN2-PadB3)") (class "Default")
      (node (ref "J2") (pin "B3") (pinfunction "SSTXN2_B3") (pintype "passive"))
    )
    (net (code "112") (name "unconnected-(J2-SSTXP1-PadA2)") (class "Default")
      (node (ref "J2") (pin "A2") (pinfunction "SSTXP1_A2") (pintype "passive"))
    )
    (net (code "113") (name "unconnected-(J2-SSTXP2-PadB2)") (class "Default")
      (node (ref "J2") (pin "B2") (pinfunction "SSTXP2_B2") (pintype "passive"))
    )
    (net (code "114") (name "unconnected-(J3-SBU1-PadA8)") (class "Default")
      (node (ref "J3") (pin "A8") (pinfunction "SBU1_A8") (pintype "passive"))
    )
    (net (code "115") (name "unconnected-(J3-SBU2-PadB8)") (class "Default")
      (node (ref "J3") (pin "B8") (pinfunction "SBU2_B8") (pintype "passive"))
    )
    (net (code "116") (name "unconnected-(J3-SSRXN1-PadB10)") (class "Default")
      (node (ref "J3") (pin "B10") (pinfunction "SSRXN1_B10") (pintype "passive"))
    )
    (net (code "117") (name "unconnected-(J3-SSRXN2-PadA10)") (class "Default")
      (node (ref "J3") (pin "A10") (pinfunction "SSRXN2_A10") (pintype "passive"))
    )
    (net (code "118") (name "unconnected-(J3-SSRXP1-PadB11)") (class "Default")
      (node (ref "J3") (pin "B11") (pinfunction "SSRXP1_B11") (pintype "passive"))
    )
    (net (code "119") (name "unconnected-(J3-SSRXP2-PadA11)") (class "Default")
      (node (ref "J3") (pin "A11") (pinfunction "SSRXP2_A11") (pintype "passive"))
    )
    (net (code "120") (name "unconnected-(J3-SSTXN1-PadA3)") (class "Default")
      (node (ref "J3") (pin "A3") (pinfunction "SSTXN1_A3") (pintype "passive"))
    )
    (net (code "121") (name "unconnected-(J3-SSTXN2-PadB3)") (class "Default")
      (node (ref "J3") (pin "B3") (pinfunction "SSTXN2_B3") (pintype "passive"))
    )
    (net (code "122") (name "unconnected-(J3-SSTXP1-PadA2)") (class "Default")
      (node (ref "J3") (pin "A2") (pinfunction "SSTXP1_A2") (pintype "passive"))
    )
    (net (code "123") (name "unconnected-(J3-SSTXP2-PadB2)") (class "Default")
      (node (ref "J3") (pin "B2") (pinfunction "SSTXP2_B2") (pintype "passive"))
    )
    (net (code "124") (name "unconnected-(J4-SBU1-PadA8)") (class "Default")
      (node (ref "J4") (pin "A8") (pinfunction "SBU1_A8") (pintype "passive"))
    )
    (net (code "125") (name "unconnected-(J4-SBU2-PadB8)") (class "Default")
      (node (ref "J4") (pin "B8") (pinfunction "SBU2_B8") (pintype "passive"))
    )
    (net (code "126") (name "unconnected-(J4-SSRXN1-PadB10)") (class "Default")
      (node (ref "J4") (pin "B10") (pinfunction "SSRXN1_B10") (pintype "passive"))
    )
    (net (code "127") (name "unconnected-(J4-SSRXN2-PadA10)") (class "Default")
      (node (ref "J4") (pin "A10") (pinfunction "SSRXN2_A10") (pintype "passive"))
    )
    (net (code "128") (name "unconnected-(J4-SSRXP1-PadB11)") (class "Default")
      (node (ref "J4") (pin "B11") (pinfunction "SSRXP1_B11") (pintype "passive"))
    )
    (net (code "129") (name "unconnected-(J4-SSRXP2-PadA11)") (class "Default")
      (node (ref "J4") (pin "A11") (pinfunction "SSRXP2_A11") (pintype "passive"))
    )
    (net (code "130") (name "unconnected-(J4-SSTXN1-PadA3)") (class "Default")
      (node (ref "J4") (pin "A3") (pinfunction "SSTXN1_A3") (pintype "passive"))
    )
    (net (code "131") (name "unconnected-(J4-SSTXN2-PadB3)") (class "Default")
      (node (ref "J4") (pin "B3") (pinfunction "SSTXN2_B3") (pintype "passive"))
    )
    (net (code "132") (name "unconnected-(J4-SSTXP1-PadA2)") (class "Default")
      (node (ref "J4") (pin "A2") (pinfunction "SSTXP1_A2") (pintype "passive"))
    )
    (net (code "133") (name "unconnected-(J4-SSTXP2-PadB2)") (class "Default")
      (node (ref "J4") (pin "B2") (pinfunction "SSTXP2_B2") (pintype "passive"))
    )
    (net (code "134") (name "unconnected-(J5-SBU1-PadA8)") (class "Default")
      (node (ref "J5") (pin "A8") (pinfunction "SBU1_A8") (pintype "passive"))
    )
    (net (code "135") (name "unconnected-(J5-SBU2-PadB8)") (class "Default")
      (node (ref "J5") (pin "B8") (pinfunction "SBU2_B8") (pintype "passive"))
    )
    (net (code "136") (name "unconnected-(J5-SSRXN1-PadB10)") (class "Default")
      (node (ref "J5") (pin "B10") (pinfunction "SSRXN1_B10") (pintype "passive"))
    )
    (net (code "137") (name "unconnected-(J5-SSRXN2-PadA10)") (class "Default")
      (node (ref "J5") (pin "A10") (pinfunction "SSRXN2_A10") (pintype "passive"))
    )
    (net (code "138") (name "unconnected-(J5-SSRXP1-PadB11)") (class "Default")
      (node (ref "J5") (pin "B11") (pinfunction "SSRXP1_B11") (pintype "passive"))
    )
    (net (code "139") (name "unconnected-(J5-SSRXP2-PadA11)") (class "Default")
      (node (ref "J5") (pin "A11") (pinfunction "SSRXP2_A11") (pintype "passive"))
    )
    (net (code "140") (name "unconnected-(J5-SSTXN1-PadA3)") (class "Default")
      (node (ref "J5") (pin "A3") (pinfunction "SSTXN1_A3") (pintype "passive"))
    )
    (net (code "141") (name "unconnected-(J5-SSTXN2-PadB3)") (class "Default")
      (node (ref "J5") (pin "B3") (pinfunction "SSTXN2_B3") (pintype "passive"))
    )
    (net (code "142") (name "unconnected-(J5-SSTXP1-PadA2)") (class "Default")
      (node (ref "J5") (pin "A2") (pinfunction "SSTXP1_A2") (pintype "passive"))
    )
    (net (code "143") (name "unconnected-(J5-SSTXP2-PadB2)") (class "Default")
      (node (ref "J5") (pin "B2") (pinfunction "SSTXP2_B2") (pintype "passive"))
    )
    (net (code "144") (name "unconnected-(J8-Pad3)") (class "Default")
      (node (ref "J8") (pin "3") (pinfunction "3_3") (pintype "bidirectional"))
    )
    (net (code "145") (name "unconnected-(J8-Pad4)") (class "Default")
      (node (ref "J8") (pin "4") (pinfunction "4_4") (pintype "bidirectional"))
    )
  )
)
